# sensor.net
KiCad netlist of a schematic drawn in EAGLE
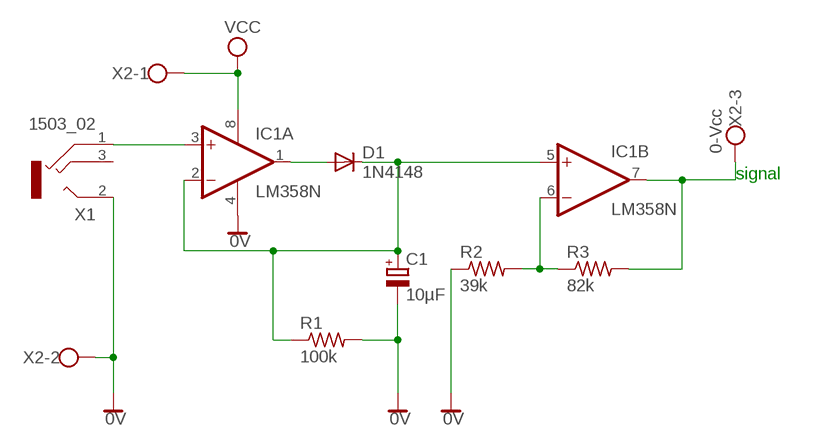
[diagram p0: schematic, sheet 1]

(export (version "E")
  (design (tool "Eeschema 10.0.6"))
  (components
    (comp (ref "C1")
      (value "10µF")
      (footprint "eagle-import:E2,5-6E")
      (libsource (lib "eagle-import") (part "CPOL-EUE2,5-6E"))
    )
    (comp (ref "D1")
      (value "1N4148")
      (footprint "eagle-import:DO35-10")
      (libsource (lib "eagle-import") (part "1N4148DO35-10"))
    )
    (comp (ref "IC1")
      (value "LM358N")
      (footprint "eagle-import:DIL08")
      (libsource (lib "eagle-import") (part "LM358N"))
    )
    (comp (ref "R1")
      (value "100k")
      (footprint "eagle-import:0207_10")
      (libsource (lib "eagle-import") (part "R-US_0207/10"))
    )
    (comp (ref "R2")
      (value "39k")
      (footprint "eagle-import:0207_10")
      (libsource (lib "eagle-import") (part "R-US_0207/10"))
    )
    (comp (ref "R3")
      (value "82k")
      (footprint "eagle-import:0207_10")
      (libsource (lib "eagle-import") (part "R-US_0207/10"))
    )
    (comp (ref "X1")
      (value "1503_02")
      (footprint "eagle-import:1503_02")
      (libsource (lib "eagle-import") (part "1503_02"))
    )
    (comp (ref "X2")
      (value "0-Vcc")
      (footprint "eagle-import:W237-103")
      (fields (field (name "MPN") "237-103"))
      (libsource (lib "eagle-import") (part "W237-103"))
    )
  )
  (nets
    (net (code "1") (name "0V") (class "Default")
      (node (ref "C1") (pin "-") (pinfunction "-_-") (pintype "passive"))
      (node (ref "IC1") (pin "4") (pinfunction "V-_4") (pintype "power_in"))
      (node (ref "R1") (pin "2") (pinfunction "2_2") (pintype "passive"))
      (node (ref "R2") (pin "1") (pinfunction "1_1") (pintype "passive"))
      (node (ref "X1") (pin "2") (pinfunction "2_2") (pintype "passive"))
      (node (ref "X2") (pin "2") (pinfunction "KL_2") (pintype "passive"))
    )
    (net (code "2") (name "Net-(IC1A-+IN)") (class "Default")
      (node (ref "IC1") (pin "3") (pinfunction "+IN_3") (pintype "input"))
      (node (ref "X1") (pin "1") (pinfunction "1_1") (pintype "passive"))
    )
    (net (code "3") (name "Net-(IC1A--IN)") (class "Default")
      (node (ref "C1") (pin "+") (pinfunction "+_+") (pintype "passive"))
      (node (ref "D1") (pin "C") (pinfunction "C_C") (pintype "passive"))
      (node (ref "IC1") (pin "2") (pinfunction "-IN_2") (pintype "input"))
      (node (ref "IC1") (pin "5") (pinfunction "+IN_5") (pintype "input"))
      (node (ref "R1") (pin "1") (pinfunction "1_1") (pintype "passive"))
    )
    (net (code "4") (name "Net-(IC1A-OUT)") (class "Default")
      (node (ref "D1") (pin "A") (pinfunction "A_A") (pintype "passive"))
      (node (ref "IC1") (pin "1") (pinfunction "OUT_1") (pintype "output"))
    )
    (net (code "5") (name "Net-(IC1B--IN)") (class "Default")
      (node (ref "IC1") (pin "6") (pinfunction "-IN_6") (pintype "input"))
      (node (ref "R2") (pin "2") (pinfunction "2_2") (pintype "passive"))
      (node (ref "R3") (pin "1") (pinfunction "1_1") (pintype "passive"))
    )
    (net (code "6") (name "Net-(IC1B-OUT)") (class "Default")
      (node (ref "IC1") (pin "7") (pinfunction "OUT_7") (pintype "output"))
      (node (ref "R3") (pin "2") (pinfunction "2_2") (pintype "passive"))
      (node (ref "X2") (pin "3") (pinfunction "KL_3") (pintype "passive"))
    )
    (net (code "7") (name "VCC") (class "Default")
      (node (ref "IC1") (pin "8") (pinfunction "V+_8") (pintype "power_in"))
      (node (ref "X2") (pin "1") (pinfunction "KL_1") (pintype "passive"))
    )
    (net (code "8") (name "unconnected-(X1-2-Pad2@2)") (class "Default")
      (node (ref "X1") (pin "2@2") (pinfunction "2_2@2") (pintype "passive"))
    )
    (net (code "9") (name "unconnected-(X1-Pad3)") (class "Default")
      (node (ref "X1") (pin "3") (pinfunction "3_3") (pintype "passive"))
    )
  )
)
